# USB.net
KiCad netlist of a schematic drawn in EasyEDA Pro
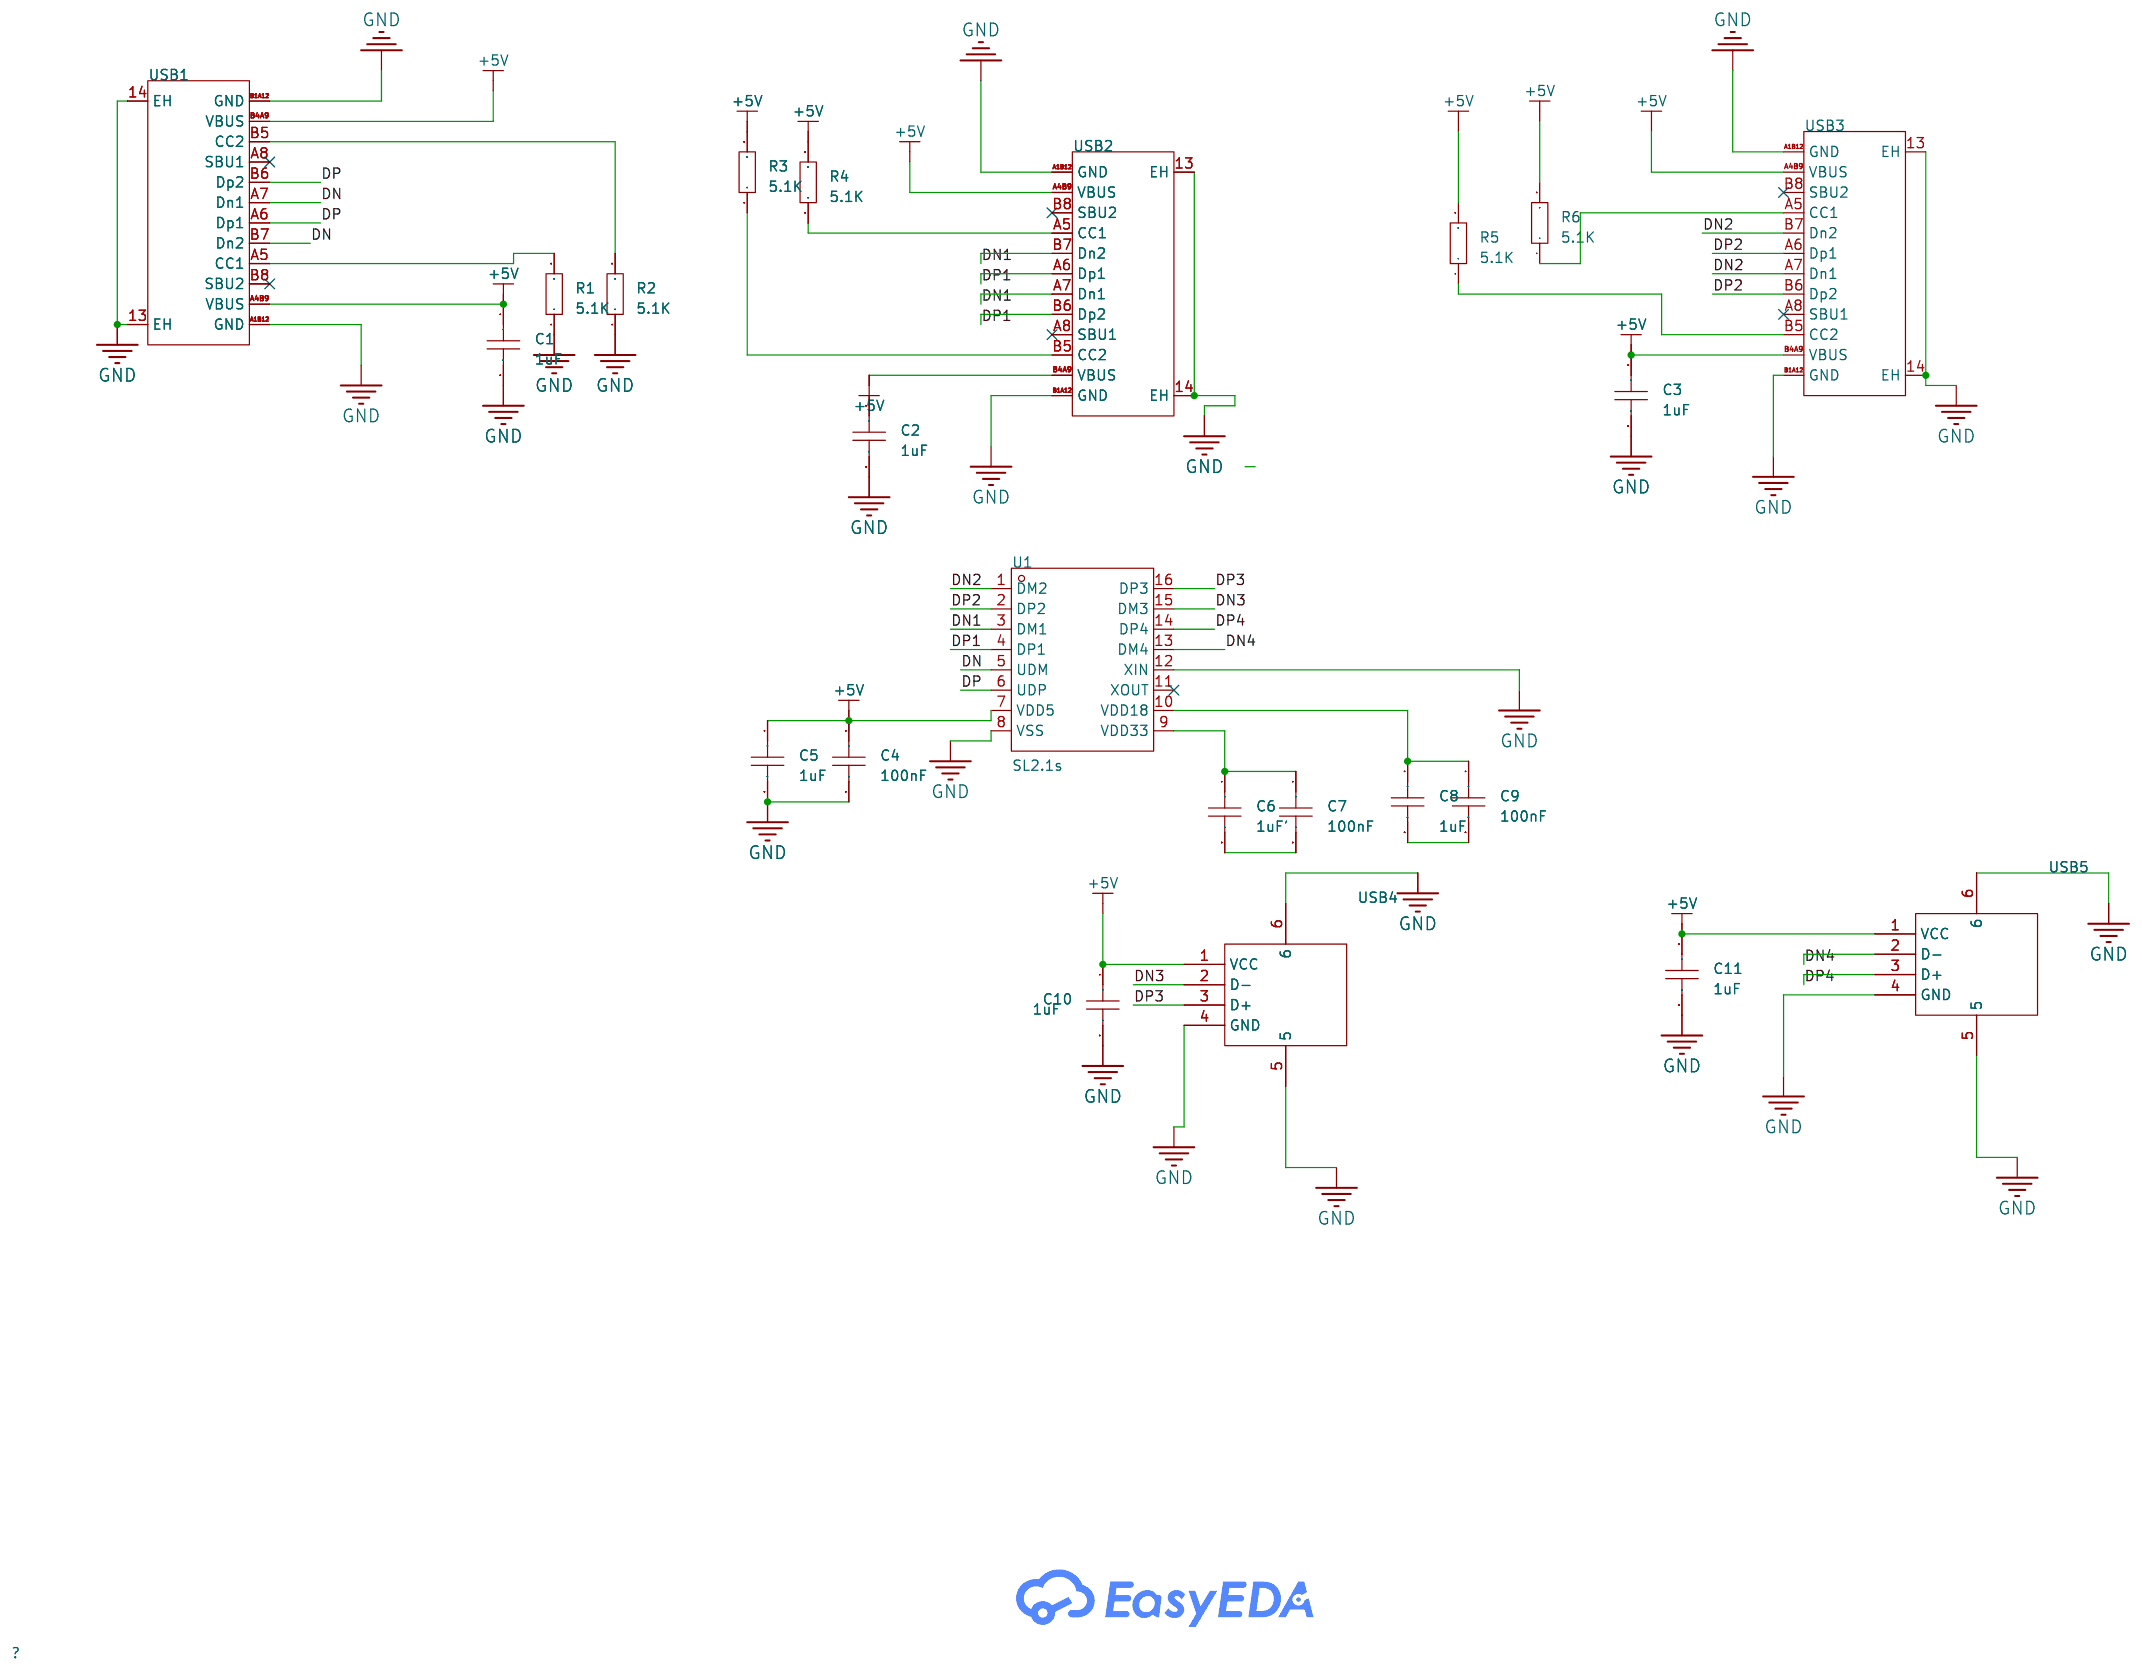
[diagram p0: schematic sheet]

(export (version "E")
  (design (tool "Eeschema 10.0.6"))
  (components
    (comp (ref "C1") (value "1uF") (footprint "easyedapro:C0603") (libsource (lib "easyedapro") (part "CAP")))
    (comp (ref "C2") (value "1uF") (footprint "easyedapro:C0603") (libsource (lib "easyedapro") (part "CAP")))
    (comp (ref "C3") (value "1uF") (footprint "easyedapro:C0603") (libsource (lib "easyedapro") (part "CAP")))
    (comp (ref "C4")
      (value "100nF")
      (footprint "easyedapro:C0603")
      (libsource (lib "easyedapro") (part "CAP"))
    )
    (comp (ref "C5") (value "1uF") (footprint "easyedapro:C0603") (libsource (lib "easyedapro") (part "CAP")))
    (comp (ref "C6")
      (value "1uF'")
      (footprint "easyedapro:C0603")
      (libsource (lib "easyedapro") (part "CAP"))
    )
    (comp (ref "C7")
      (value "100nF")
      (footprint "easyedapro:C0603")
      (libsource (lib "easyedapro") (part "CAP"))
    )
    (comp (ref "C8") (value "1uF") (footprint "easyedapro:C0603") (libsource (lib "easyedapro") (part "CAP")))
    (comp (ref "C9")
      (value "100nF")
      (footprint "easyedapro:C0603")
      (libsource (lib "easyedapro") (part "CAP"))
    )
    (comp (ref "C10")
      (value "1uF")
      (footprint "easyedapro:C0603")
      (libsource (lib "easyedapro") (part "CAP"))
    )
    (comp (ref "C11")
      (value "1uF")
      (footprint "easyedapro:C0603")
      (libsource (lib "easyedapro") (part "CAP"))
    )
    (comp (ref "R1")
      (value "5.1K")
      (footprint "easyedapro:R0603")
      (libsource (lib "easyedapro") (part "Res"))
    )
    (comp (ref "R2")
      (value "5.1K")
      (footprint "easyedapro:R0603")
      (libsource (lib "easyedapro") (part "Res"))
    )
    (comp (ref "R3")
      (value "5.1K")
      (footprint "easyedapro:R0603")
      (libsource (lib "easyedapro") (part "Res"))
    )
    (comp (ref "R4")
      (value "5.1K")
      (footprint "easyedapro:R0603")
      (libsource (lib "easyedapro") (part "Res"))
    )
    (comp (ref "R5")
      (value "5.1K")
      (footprint "easyedapro:R0603")
      (libsource (lib "easyedapro") (part "Res"))
    )
    (comp (ref "R6")
      (value "5.1K")
      (footprint "easyedapro:R0603")
      (libsource (lib "easyedapro") (part "Res"))
    )
    (comp (ref "U1")
      (value "SL2.1s")
      (footprint "easyedapro:SSOP-16_L4.6-W2.6-P0.53-LS4.0-BL")
      (fields (field (name "Manufacturer") "CoreChips(和芯润德)"))
      (libsource (lib "easyedapro") (part "SL2.1S"))
    )
    (comp (ref "USB1")
      (value "TYPE-C 16PIN 2MD(073)")
      (footprint "easyedapro:USB-C-SMD_TYPE-C-16PIN-2MD-073")
      (fields (field (name "Manufacturer") "SHOU HAN(首韩)"))
      (libsource (lib "easyedapro") (part "TYPE-C 16PIN 2MD(073)"))
    )
    (comp (ref "USB2")
      (value "TYPE-C 16PIN 2MD(073)")
      (footprint "easyedapro:USB-C-SMD_TYPE-C-16PIN-2MD-073")
      (fields (field (name "Manufacturer") "SHOU HAN(首韩)"))
      (libsource (lib "easyedapro") (part "TYPE-C 16PIN 2MD(073)"))
    )
    (comp (ref "USB3")
      (value "TYPE-C 16PIN 2MD(073)")
      (footprint "easyedapro:USB-C-SMD_TYPE-C-16PIN-2MD-073")
      (fields (field (name "Manufacturer") "SHOU HAN(首韩)"))
      (libsource (lib "easyedapro") (part "TYPE-C 16PIN 2MD(073)"))
    )
    (comp (ref "USB4")
      (value "10.0 QHHTZB6.3")
      (footprint "easyedapro:USB-A-TH_10.0QHHTZB6.3")
      (fields (field (name "Manufacturer") "SHOU HAN(首韩)"))
      (libsource (lib "easyedapro") (part "10.0 QHHTZB6.3"))
    )
    (comp (ref "USB5")
      (value "10.0 QHHTZB6.3")
      (footprint "easyedapro:USB-A-TH_10.0QHHTZB6.3")
      (fields (field (name "Manufacturer") "SHOU HAN(首韩)"))
      (libsource (lib "easyedapro") (part "10.0 QHHTZB6.3"))
    )
  )
  (nets
    (net (code "1") (name "+5V") (class "Default")
      (node (ref "C1") (pin "1") (pinfunction "1_1") (pintype "input"))
      (node (ref "C10") (pin "1") (pinfunction "1_1") (pintype "input"))
      (node (ref "C11") (pin "1") (pinfunction "1_1") (pintype "input"))
      (node (ref "C3") (pin "1") (pinfunction "1_1") (pintype "input"))
      (node (ref "C4") (pin "1") (pinfunction "1_1") (pintype "input"))
      (node (ref "C5") (pin "1") (pinfunction "1_1") (pintype "input"))
      (node (ref "R3") (pin "2") (pinfunction "2_2") (pintype "input"))
      (node (ref "R4") (pin "2") (pinfunction "2_2") (pintype "input"))
      (node (ref "R5") (pin "2") (pinfunction "2_2") (pintype "input"))
      (node (ref "R6") (pin "2") (pinfunction "2_2") (pintype "input"))
      (node (ref "U1") (pin "7") (pinfunction "VDD5_7") (pintype "unspecified"))
      (node (ref "USB1") (pin "A4B9") (pinfunction "VBUS_A4B9") (pintype "unspecified"))
      (node (ref "USB1") (pin "B4A9") (pinfunction "VBUS_B4A9") (pintype "unspecified"))
      (node (ref "USB2") (pin "A4B9") (pinfunction "VBUS_A4B9") (pintype "unspecified"))
      (node (ref "USB2") (pin "B4A9") (pinfunction "VBUS_B4A9") (pintype "unspecified"))
      (node (ref "USB3") (pin "A4B9") (pinfunction "VBUS_A4B9") (pintype "unspecified"))
      (node (ref "USB3") (pin "B4A9") (pinfunction "VBUS_B4A9") (pintype "unspecified"))
      (node (ref "USB4") (pin "1") (pinfunction "VCC_1") (pintype "unspecified"))
      (node (ref "USB5") (pin "1") (pinfunction "VCC_1") (pintype "unspecified"))
    )
    (net (code "2") (name "/DN") (class "Default")
      (node (ref "U1") (pin "5") (pinfunction "UDM_5") (pintype "unspecified"))
      (node (ref "USB1") (pin "A7") (pinfunction "Dn1_A7") (pintype "unspecified"))
      (node (ref "USB1") (pin "B7") (pinfunction "Dn2_B7") (pintype "unspecified"))
    )
    (net (code "3") (name "/DN1") (class "Default")
      (node (ref "U1") (pin "3") (pinfunction "DM1_3") (pintype "unspecified"))
      (node (ref "USB2") (pin "A7") (pinfunction "Dn1_A7") (pintype "unspecified"))
      (node (ref "USB2") (pin "B7") (pinfunction "Dn2_B7") (pintype "unspecified"))
    )
    (net (code "4") (name "/DN2") (class "Default")
      (node (ref "U1") (pin "1") (pinfunction "DM2_1") (pintype "unspecified"))
      (node (ref "USB3") (pin "A7") (pinfunction "Dn1_A7") (pintype "unspecified"))
      (node (ref "USB3") (pin "B7") (pinfunction "Dn2_B7") (pintype "unspecified"))
    )
    (net (code "5") (name "/DN3") (class "Default")
      (node (ref "U1") (pin "15") (pinfunction "DM3_15") (pintype "unspecified"))
      (node (ref "USB4") (pin "2") (pinfunction "D-_2") (pintype "unspecified"))
    )
    (net (code "6") (name "/DN4") (class "Default")
      (node (ref "U1") (pin "13") (pinfunction "DM4_13") (pintype "unspecified"))
      (node (ref "USB5") (pin "2") (pinfunction "D-_2") (pintype "unspecified"))
    )
    (net (code "7") (name "/DP") (class "Default")
      (node (ref "U1") (pin "6") (pinfunction "UDP_6") (pintype "unspecified"))
      (node (ref "USB1") (pin "A6") (pinfunction "Dp1_A6") (pintype "unspecified"))
      (node (ref "USB1") (pin "B6") (pinfunction "Dp2_B6") (pintype "unspecified"))
    )
    (net (code "8") (name "/DP1") (class "Default")
      (node (ref "U1") (pin "4") (pinfunction "DP1_4") (pintype "unspecified"))
      (node (ref "USB2") (pin "A6") (pinfunction "Dp1_A6") (pintype "unspecified"))
      (node (ref "USB2") (pin "B6") (pinfunction "Dp2_B6") (pintype "unspecified"))
    )
    (net (code "9") (name "/DP2") (class "Default")
      (node (ref "U1") (pin "2") (pinfunction "DP2_2") (pintype "unspecified"))
      (node (ref "USB3") (pin "A6") (pinfunction "Dp1_A6") (pintype "unspecified"))
      (node (ref "USB3") (pin "B6") (pinfunction "Dp2_B6") (pintype "unspecified"))
    )
    (net (code "10") (name "/DP3") (class "Default")
      (node (ref "U1") (pin "16") (pinfunction "DP3_16") (pintype "unspecified"))
      (node (ref "USB4") (pin "3") (pinfunction "D+_3") (pintype "unspecified"))
    )
    (net (code "11") (name "/DP4") (class "Default")
      (node (ref "U1") (pin "14") (pinfunction "DP4_14") (pintype "unspecified"))
      (node (ref "USB5") (pin "3") (pinfunction "D+_3") (pintype "unspecified"))
    )
    (net (code "12") (name "GND") (class "Default")
      (node (ref "C1") (pin "2") (pinfunction "2_2") (pintype "input"))
      (node (ref "C10") (pin "2") (pinfunction "2_2") (pintype "input"))
      (node (ref "C11") (pin "2") (pinfunction "2_2") (pintype "input"))
      (node (ref "C2") (pin "2") (pinfunction "2_2") (pintype "input"))
      (node (ref "C3") (pin "2") (pinfunction "2_2") (pintype "input"))
      (node (ref "C4") (pin "2") (pinfunction "2_2") (pintype "input"))
      (node (ref "C5") (pin "2") (pinfunction "2_2") (pintype "input"))
      (node (ref "R1") (pin "1") (pinfunction "1_1") (pintype "input"))
      (node (ref "R2") (pin "1") (pinfunction "1_1") (pintype "input"))
      (node (ref "U1") (pin "12") (pinfunction "XIN_12") (pintype "unspecified"))
      (node (ref "U1") (pin "8") (pinfunction "VSS_8") (pintype "unspecified"))
      (node (ref "USB1") (pin "13") (pinfunction "EH_13") (pintype "unspecified"))
      (node (ref "USB1") (pin "14") (pinfunction "EH_14") (pintype "unspecified"))
      (node (ref "USB1") (pin "A1B12") (pinfunction "GND_A1B12") (pintype "unspecified"))
      (node (ref "USB1") (pin "B1A12") (pinfunction "GND_B1A12") (pintype "unspecified"))
      (node (ref "USB2") (pin "13") (pinfunction "EH_13") (pintype "unspecified"))
      (node (ref "USB2") (pin "14") (pinfunction "EH_14") (pintype "unspecified"))
      (node (ref "USB2") (pin "A1B12") (pinfunction "GND_A1B12") (pintype "unspecified"))
      (node (ref "USB2") (pin "B1A12") (pinfunction "GND_B1A12") (pintype "unspecified"))
      (node (ref "USB3") (pin "13") (pinfunction "EH_13") (pintype "unspecified"))
      (node (ref "USB3") (pin "14") (pinfunction "EH_14") (pintype "unspecified"))
      (node (ref "USB3") (pin "A1B12") (pinfunction "GND_A1B12") (pintype "unspecified"))
      (node (ref "USB3") (pin "B1A12") (pinfunction "GND_B1A12") (pintype "unspecified"))
      (node (ref "USB4") (pin "4") (pinfunction "GND_4") (pintype "unspecified"))
      (node (ref "USB4") (pin "5") (pinfunction "5_5") (pintype "unspecified"))
      (node (ref "USB4") (pin "6") (pinfunction "6_6") (pintype "unspecified"))
      (node (ref "USB5") (pin "4") (pinfunction "GND_4") (pintype "unspecified"))
      (node (ref "USB5") (pin "5") (pinfunction "5_5") (pintype "unspecified"))
      (node (ref "USB5") (pin "6") (pinfunction "6_6") (pintype "unspecified"))
    )
    (net (code "13") (name "Net-(C6-Pad2)") (class "Default")
      (node (ref "C6") (pin "2") (pinfunction "2_2") (pintype "input"))
      (node (ref "C7") (pin "2") (pinfunction "2_2") (pintype "input"))
    )
    (net (code "14") (name "Net-(C8-Pad2)") (class "Default")
      (node (ref "C8") (pin "2") (pinfunction "2_2") (pintype "input"))
      (node (ref "C9") (pin "2") (pinfunction "2_2") (pintype "input"))
    )
    (net (code "15") (name "Net-(U1-VDD18)") (class "Default")
      (node (ref "C8") (pin "1") (pinfunction "1_1") (pintype "input"))
      (node (ref "C9") (pin "1") (pinfunction "1_1") (pintype "input"))
      (node (ref "U1") (pin "10") (pinfunction "VDD18_10") (pintype "unspecified"))
    )
    (net (code "16") (name "Net-(U1-VDD33)") (class "Default")
      (node (ref "C6") (pin "1") (pinfunction "1_1") (pintype "input"))
      (node (ref "C7") (pin "1") (pinfunction "1_1") (pintype "input"))
      (node (ref "U1") (pin "9") (pinfunction "VDD33_9") (pintype "unspecified"))
    )
    (net (code "17") (name "Net-(USB1-CC1)") (class "Default")
      (node (ref "R1") (pin "2") (pinfunction "2_2") (pintype "input"))
      (node (ref "USB1") (pin "A5") (pinfunction "CC1_A5") (pintype "unspecified"))
    )
    (net (code "18") (name "Net-(USB1-CC2)") (class "Default")
      (node (ref "R2") (pin "2") (pinfunction "2_2") (pintype "input"))
      (node (ref "USB1") (pin "B5") (pinfunction "CC2_B5") (pintype "unspecified"))
    )
    (net (code "19") (name "Net-(USB2-CC1)") (class "Default")
      (node (ref "R4") (pin "1") (pinfunction "1_1") (pintype "input"))
      (node (ref "USB2") (pin "A5") (pinfunction "CC1_A5") (pintype "unspecified"))
    )
    (net (code "20") (name "Net-(USB2-CC2)") (class "Default")
      (node (ref "R3") (pin "1") (pinfunction "1_1") (pintype "input"))
      (node (ref "USB2") (pin "B5") (pinfunction "CC2_B5") (pintype "unspecified"))
    )
    (net (code "21") (name "Net-(USB3-CC1)") (class "Default")
      (node (ref "R6") (pin "1") (pinfunction "1_1") (pintype "input"))
      (node (ref "USB3") (pin "A5") (pinfunction "CC1_A5") (pintype "unspecified"))
    )
    (net (code "22") (name "Net-(USB3-CC2)") (class "Default")
      (node (ref "R5") (pin "1") (pinfunction "1_1") (pintype "input"))
      (node (ref "USB3") (pin "B5") (pinfunction "CC2_B5") (pintype "unspecified"))
    )
    (net (code "23") (name "unconnected-(C2-Pad1)") (class "Default")
      (node (ref "C2") (pin "1") (pinfunction "1_1") (pintype "input"))
    )
    (net (code "24") (name "unconnected-(U1-XOUT-Pad11)") (class "Default")
      (node (ref "U1") (pin "11") (pinfunction "XOUT_11") (pintype "unspecified+no_connect"))
    )
    (net (code "25") (name "unconnected-(USB1-SBU1-PadA8)") (class "Default")
      (node (ref "USB1") (pin "A8") (pinfunction "SBU1_A8") (pintype "unspecified+no_connect"))
    )
    (net (code "26") (name "unconnected-(USB1-SBU2-PadB8)") (class "Default")
      (node (ref "USB1") (pin "B8") (pinfunction "SBU2_B8") (pintype "unspecified+no_connect"))
    )
    (net (code "27") (name "unconnected-(USB2-SBU1-PadA8)") (class "Default")
      (node (ref "USB2") (pin "A8") (pinfunction "SBU1_A8") (pintype "unspecified+no_connect"))
    )
    (net (code "28") (name "unconnected-(USB2-SBU2-PadB8)") (class "Default")
      (node (ref "USB2") (pin "B8") (pinfunction "SBU2_B8") (pintype "unspecified+no_connect"))
    )
    (net (code "29") (name "unconnected-(USB3-SBU1-PadA8)") (class "Default")
      (node (ref "USB3") (pin "A8") (pinfunction "SBU1_A8") (pintype "unspecified+no_connect"))
    )
    (net (code "30") (name "unconnected-(USB3-SBU2-PadB8)") (class "Default")
      (node (ref "USB3") (pin "B8") (pinfunction "SBU2_B8") (pintype "unspecified+no_connect"))
    )
  )
)
